# Main_Board_-_Double.net
KiCad netlist of a schematic drawn in EAGLE
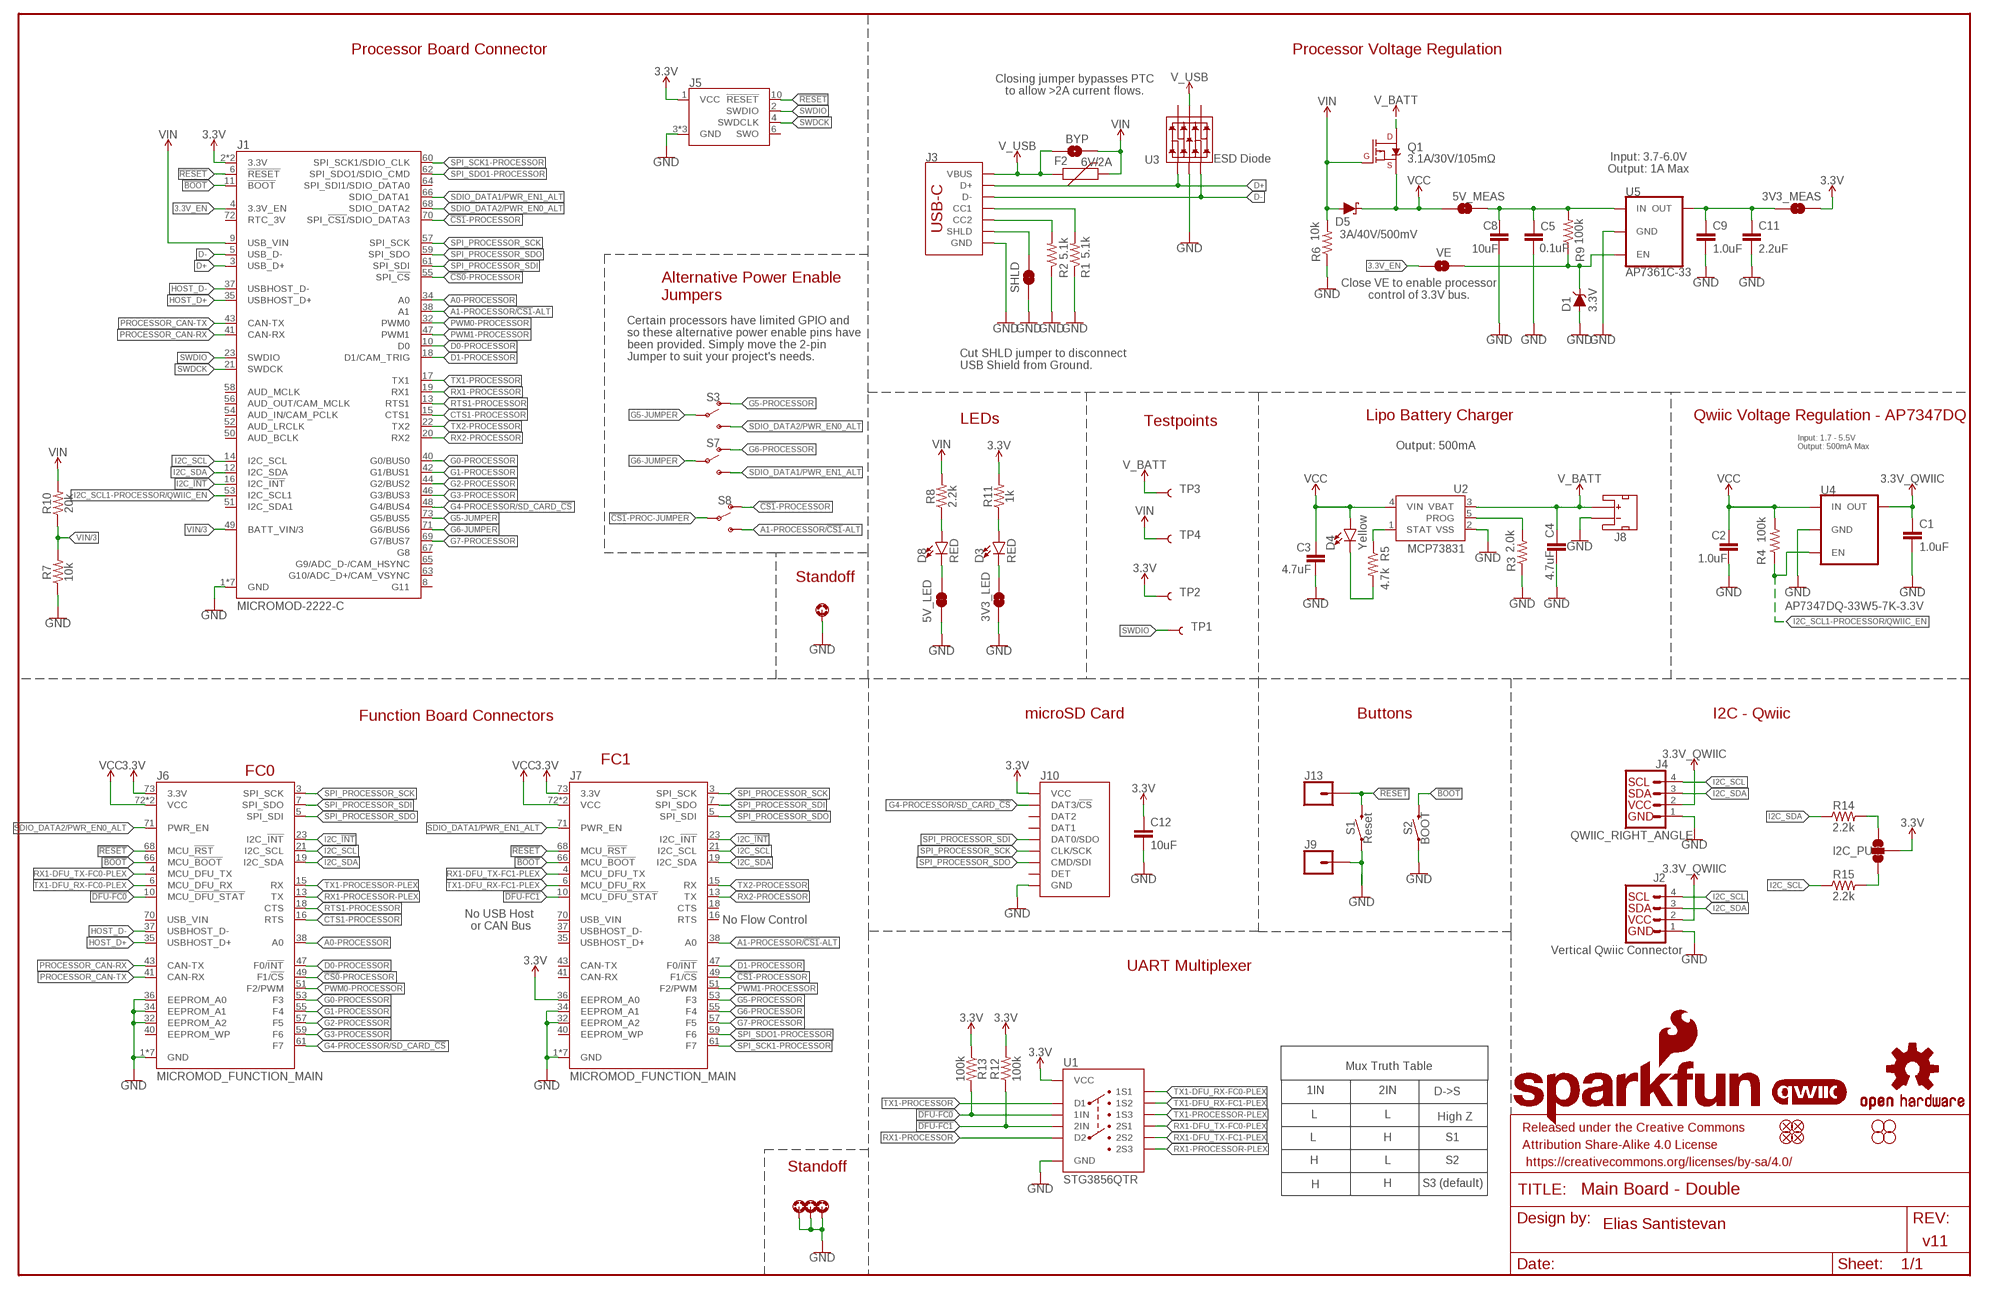
[diagram p0: schematic, sheet 1]

(export (version "E")
  (design (tool "Eeschema 10.0.6"))
  (components
    (comp (ref "3V3_LED")
      (value "JUMPER-SMT_2_NC_TRACE_SILK")
      (footprint "eagle-import:SMT-JUMPER_2_NC_TRACE_SILK")
      (libsource (lib "eagle-import") (part "JUMPER-SMT_2_NC_TRACE_SILK"))
    )
    (comp (ref "3V3_MEAS")
      (value "JUMPER-COMBO_2_NC_TRACE")
      (footprint "eagle-import:COMBO-JUMPER_2_NC_TRACE")
      (libsource (lib "eagle-import") (part "JUMPER-COMBO_2_NC_TRACE"))
    )
    (comp (ref "5V_LED")
      (value "JUMPER-SMT_2_NC_TRACE_SILK")
      (footprint "eagle-import:SMT-JUMPER_2_NC_TRACE_SILK")
      (libsource (lib "eagle-import") (part "JUMPER-SMT_2_NC_TRACE_SILK"))
    )
    (comp (ref "5V_MEAS")
      (value "JUMPER-COMBO_2_NC_TRACE")
      (footprint "eagle-import:COMBO-JUMPER_2_NC_TRACE")
      (libsource (lib "eagle-import") (part "JUMPER-COMBO_2_NC_TRACE"))
    )
    (comp (ref "BYP")
      (value "JUMPER-SMT_2_NO_SILK")
      (footprint "eagle-import:SMT-JUMPER_2_NO_SILK")
      (libsource (lib "eagle-import") (part "JUMPER-SMT_2_NO_SILK"))
    )
    (comp (ref "C1")
      (value "1.0uF")
      (footprint "eagle-import:0603")
      (libsource (lib "eagle-import") (part "1.0UF-0603-16V-10%"))
    )
    (comp (ref "C2")
      (value "1.0uF")
      (footprint "eagle-import:0603")
      (libsource (lib "eagle-import") (part "1.0UF-0603-16V-10%"))
    )
    (comp (ref "C3")
      (value "4.7uF")
      (footprint "eagle-import:0603")
      (libsource (lib "eagle-import") (part "4.7UF-0603-6.3V-(10%)"))
    )
    (comp (ref "C4")
      (value "4.7uF")
      (footprint "eagle-import:0603")
      (libsource (lib "eagle-import") (part "4.7UF-0603-35V-(20%)"))
    )
    (comp (ref "C5")
      (value "0.1uF")
      (footprint "eagle-import:0603")
      (libsource (lib "eagle-import") (part "0.1UF-0603-25V-(+80/-20%)"))
    )
    (comp (ref "C8")
      (value "10uF")
      (footprint "eagle-import:0805")
      (libsource (lib "eagle-import") (part "10UF-0805-10V-10%"))
    )
    (comp (ref "C9")
      (value "1.0uF")
      (footprint "eagle-import:0603")
      (libsource (lib "eagle-import") (part "1.0UF-0603-16V-10%"))
    )
    (comp (ref "C11")
      (value "2.2uF")
      (footprint "eagle-import:0603")
      (libsource (lib "eagle-import") (part "2.2UF-0603-10V-20%"))
    )
    (comp (ref "C12")
      (value "10uF")
      (footprint "eagle-import:0603")
      (libsource (lib "eagle-import") (part "10UF-0603-6.3V-20%"))
    )
    (comp (ref "D1")
      (value "3.3V")
      (footprint "eagle-import:SOD-323")
      (libsource (lib "eagle-import") (part "DIODE-ZENER-MM3Z3V3T1G"))
    )
    (comp (ref "D3")
      (value "RED")
      (footprint "eagle-import:LED-0603")
      (libsource (lib "eagle-import") (part "LED-RED0603"))
    )
    (comp (ref "D4")
      (value "Yellow")
      (footprint "eagle-import:LED-0603")
      (libsource (lib "eagle-import") (part "LED-YELLOW0603"))
    )
    (comp (ref "D5")
      (value "3A/40V/500mV")
      (footprint "eagle-import:SMA-DIODE")
      (libsource (lib "eagle-import") (part "DIODE-SCHOTTKY-B340A"))
    )
    (comp (ref "D8")
      (value "RED")
      (footprint "eagle-import:LED-0603")
      (libsource (lib "eagle-import") (part "LED-RED0603"))
    )
    (comp (ref "F2")
      (value "6V/2A")
      (footprint "eagle-import:1210")
      (libsource (lib "eagle-import") (part "PPTC_6V2A"))
    )
    (comp (ref "FD1")
      (value "FIDUCIAL1X2")
      (footprint "eagle-import:FIDUCIAL-1X2")
      (libsource (lib "eagle-import") (part "FIDUCIAL1X2"))
    )
    (comp (ref "FD2")
      (value "FIDUCIAL1X2")
      (footprint "eagle-import:FIDUCIAL-1X2")
      (libsource (lib "eagle-import") (part "FIDUCIAL1X2"))
    )
    (comp (ref "FD3")
      (value "FIDUCIAL1X2")
      (footprint "eagle-import:FIDUCIAL-1X2")
      (libsource (lib "eagle-import") (part "FIDUCIAL1X2"))
    )
    (comp (ref "FD4")
      (value "FIDUCIAL1X2")
      (footprint "eagle-import:FIDUCIAL-1X2")
      (libsource (lib "eagle-import") (part "FIDUCIAL1X2"))
    )
    (comp (ref "FRAME1")
      (value "FRAME-LEDGER")
      (footprint "eagle-import:CREATIVE_COMMONS")
      (libsource (lib "eagle-import") (part "FRAME-LEDGER"))
    )
    (comp (ref "H2")
      (value "STAND-OFF-REFLOW-M2.5_2.5MM_TALL")
      (footprint "eagle-import:STAND-OFF-REFLOW-M2.5")
      (libsource (lib "eagle-import") (part "STAND-OFF-REFLOW-M2.5_2.5MM_TALL"))
    )
    (comp (ref "H3")
      (value "STAND-OFF-REFLOW-M2.5_2.5MM_TALL")
      (footprint "eagle-import:STAND-OFF-REFLOW-M2.5")
      (libsource (lib "eagle-import") (part "STAND-OFF-REFLOW-M2.5_2.5MM_TALL"))
    )
    (comp (ref "H4")
      (value "STAND-OFF-REFLOW-M2.5_2.5MM_TALL")
      (footprint "eagle-import:STAND-OFF-REFLOW-M2.5")
      (libsource (lib "eagle-import") (part "STAND-OFF-REFLOW-M2.5_2.5MM_TALL"))
    )
    (comp (ref "H8")
      (value "STAND-OFF-REFLOW-M2.5_2.5MM_TALL")
      (footprint "eagle-import:STAND-OFF-REFLOW-M2.5")
      (libsource (lib "eagle-import") (part "STAND-OFF-REFLOW-M2.5_2.5MM_TALL"))
    )
    (comp (ref "H14")
      (value "STAND-OFFTIGHT")
      (footprint "eagle-import:STAND-OFF-TIGHT")
      (libsource (lib "eagle-import") (part "STAND-OFFTIGHT"))
    )
    (comp (ref "H15")
      (value "STAND-OFFTIGHT")
      (footprint "eagle-import:STAND-OFF-TIGHT")
      (libsource (lib "eagle-import") (part "STAND-OFFTIGHT"))
    )
    (comp (ref "H16")
      (value "STAND-OFFTIGHT")
      (footprint "eagle-import:STAND-OFF-TIGHT")
      (libsource (lib "eagle-import") (part "STAND-OFFTIGHT"))
    )
    (comp (ref "H17")
      (value "STAND-OFFTIGHT")
      (footprint "eagle-import:STAND-OFF-TIGHT")
      (libsource (lib "eagle-import") (part "STAND-OFFTIGHT"))
    )
    (comp (ref "I2C_PU")
      (value "JUMPER-SMT_3_2-NC_TRACE_SILK")
      (footprint "eagle-import:SMT-JUMPER_3_2-NC_TRACE_SILK")
      (libsource (lib "eagle-import") (part "JUMPER-SMT_3_2-NC_TRACE_SILK"))
    )
    (comp (ref "J1")
      (value "MICROMOD-2222-C")
      (footprint "eagle-import:M.2-CONNECTOR-E")
      (libsource (lib "eagle-import") (part "MICROMOD-2222-C"))
    )
    (comp (ref "J2")
      (value "Vertical Qwiic Connector")
      (footprint "eagle-import:JST04_1MM_VERT")
      (libsource (lib "eagle-import") (part "QWIIC_CONNECTOR"))
    )
    (comp (ref "J3")
      (value "USB_C_2-LAYER_PADS")
      (footprint "eagle-import:USB-C-16P-2LAYER-PADS")
      (libsource (lib "eagle-import") (part "USB_C_2-LAYER_PADS"))
    )
    (comp (ref "J4")
      (value "QWIIC_RIGHT_ANGLE")
      (footprint "eagle-import:JST04_1MM_RA")
      (libsource (lib "eagle-import") (part "QWIIC_CONNECTORJS-1MM"))
    )
    (comp (ref "J5")
      (value "CORTEX_JTAG_DEBUG_MINIMUM_PTH")
      (footprint "eagle-import:2X5-PTH-1.27MM")
      (libsource (lib "eagle-import") (part "CORTEX_JTAG_DEBUG_MINIMUM_PTH"))
    )
    (comp (ref "J6")
      (value "MICROMOD_FUNCTION_MAIN")
      (footprint "eagle-import:M.2-CONNECTOR-E-FUNCTION-STANDARD")
      (libsource (lib "eagle-import") (part "MICROMOD_FUNCTION_MAIN"))
    )
    (comp (ref "J7")
      (value "MICROMOD_FUNCTION_MAIN")
      (footprint "eagle-import:M.2-CONNECTOR-E-FUNCTION-STANDARD")
      (libsource (lib "eagle-import") (part "MICROMOD_FUNCTION_MAIN"))
    )
    (comp (ref "J8")
      (value "JST_2MM_MALE")
      (footprint "eagle-import:JST-2-SMD")
      (libsource (lib "eagle-import") (part "JST_2MM_MALE"))
    )
    (comp (ref "J9")
      (value "CONN_01PTH_NO_SILK_YES_STOP")
      (footprint "eagle-import:1X01_NO_SILK")
      (libsource (lib "eagle-import") (part "CONN_01PTH_NO_SILK_YES_STOP"))
    )
    (comp (ref "J10")
      (value "MICRO-SD-PUSH-PUSH-EXT-PIN")
      (footprint "eagle-import:MICROSD-EXTERNALPIN")
      (libsource (lib "eagle-import") (part "MICRO-SD-PUSH-PUSH-EXT-PIN"))
    )
    (comp (ref "J13")
      (value "CONN_01PTH_NO_SILK_YES_STOP")
      (footprint "eagle-import:1X01_NO_SILK")
      (libsource (lib "eagle-import") (part "CONN_01PTH_NO_SILK_YES_STOP"))
    )
    (comp (ref "LOGO1")
      (value "QWIIC_LOGO_8MM")
      (footprint "eagle-import:QWIIC_8MM")
      (libsource (lib "eagle-import") (part "QWIIC_LOGO_8MM"))
    )
    (comp (ref "LOGO2")
      (value "SFE_LOGO_NAME_FLAME.3_INCH")
      (footprint "eagle-import:SFE_LOGO_NAME_FLAME_.3")
      (libsource (lib "eagle-import") (part "SFE_LOGO_NAME_FLAME.3_INCH"))
    )
    (comp (ref "LOGO3")
      (value "OSHW-LOGOL")
      (footprint "eagle-import:OSHW-LOGO-L")
      (libsource (lib "eagle-import") (part "OSHW-LOGOL"))
    )
    (comp (ref "Q1")
      (value "3.1A/30V/105mΩ")
      (footprint "eagle-import:SOT23-3")
      (libsource (lib "eagle-import") (part "MOSFET_PCH-DMG2307L"))
    )
    (comp (ref "R1")
      (value "5.1k")
      (footprint "eagle-import:0603")
      (libsource (lib "eagle-import") (part "5.1KOHM5.1KOHM-0603-1/10W-1%"))
    )
    (comp (ref "R2")
      (value "5.1k")
      (footprint "eagle-import:0603")
      (libsource (lib "eagle-import") (part "5.1KOHM5.1KOHM-0603-1/10W-1%"))
    )
    (comp (ref "R3")
      (value "2.0k")
      (footprint "eagle-import:0603")
      (libsource (lib "eagle-import") (part "2.0KOHM-0603-1/10W-5%"))
    )
    (comp (ref "R4")
      (value "100k")
      (footprint "eagle-import:0603")
      (libsource (lib "eagle-import") (part "100KOHM-0603-1/10W-1%"))
    )
    (comp (ref "R5")
      (value "4.7k")
      (footprint "eagle-import:0603")
      (libsource (lib "eagle-import") (part "4.7KOHM-0603-1/10W-1%"))
    )
    (comp (ref "R6")
      (value "10k")
      (footprint "eagle-import:0603")
      (libsource (lib "eagle-import") (part "10KOHM-0603-1/10W-1%"))
    )
    (comp (ref "R7")
      (value "10k")
      (footprint "eagle-import:0603")
      (libsource (lib "eagle-import") (part "10KOHM-0603-1/10W-1%"))
    )
    (comp (ref "R8")
      (value "2.2k")
      (footprint "eagle-import:0603")
      (libsource (lib "eagle-import") (part "2.2KOHM-0603-1/10W-1%"))
    )
    (comp (ref "R9")
      (value "100k")
      (footprint "eagle-import:0603")
      (libsource (lib "eagle-import") (part "100KOHM-0603-1/10W-1%"))
    )
    (comp (ref "R10")
      (value "20k")
      (footprint "eagle-import:0603")
      (libsource (lib "eagle-import") (part "20KOHM-0603-1/10W-1%"))
    )
    (comp (ref "R11")
      (value "1k")
      (footprint "eagle-import:0603")
      (libsource (lib "eagle-import") (part "1KOHM-0603-1/10W-1%"))
    )
    (comp (ref "R12")
      (value "100k")
      (footprint "eagle-import:0603")
      (libsource (lib "eagle-import") (part "100KOHM-0603-1/10W-1%"))
    )
    (comp (ref "R13")
      (value "100k")
      (footprint "eagle-import:0603")
      (libsource (lib "eagle-import") (part "100KOHM-0603-1/10W-1%"))
    )
    (comp (ref "R14")
      (value "2.2k")
      (footprint "eagle-import:0603")
      (libsource (lib "eagle-import") (part "2.2KOHM-0603-1/10W-1%"))
    )
    (comp (ref "R15")
      (value "2.2k")
      (footprint "eagle-import:0603")
      (libsource (lib "eagle-import") (part "2.2KOHM-0603-1/10W-1%"))
    )
    (comp (ref "S1")
      (value "Reset")
      (footprint "eagle-import:TACTILE_SWITCH_SMD_5.2MM")
      (libsource (lib "eagle-import") (part "MOMENTARY-SWITCH-SPST-SMD-5.2-TALL-REDUNDANT"))
    )
    (comp (ref "S2")
      (value "BOOT")
      (footprint "eagle-import:TACTILE_SWITCH_SMD_5.2MM")
      (libsource (lib "eagle-import") (part "MOMENTARY-SWITCH-SPST-SMD-5.2-TALL-REDUNDANT"))
    )
    (comp (ref "S3")
      (value "SWITCH-SPDT-SMD-RIGHT-ANGLE")
      (footprint "eagle-import:SWITCH_SPST_SMD_A")
      (libsource (lib "eagle-import") (part "SWITCH-SPDT-SMD-RIGHT-ANGLE"))
    )
    (comp (ref "S7")
      (value "SWITCH-SPDT-SMD-RIGHT-ANGLE")
      (footprint "eagle-import:SWITCH_SPST_SMD_A")
      (libsource (lib "eagle-import") (part "SWITCH-SPDT-SMD-RIGHT-ANGLE"))
    )
    (comp (ref "S8")
      (value "SWITCH-SPDT-SMD-RIGHT-ANGLE")
      (footprint "eagle-import:SWITCH_SPST_SMD_A")
      (libsource (lib "eagle-import") (part "SWITCH-SPDT-SMD-RIGHT-ANGLE"))
    )
    (comp (ref "SHLD")
      (value "JUMPER-SMT_2_NC_TRACE_SILK")
      (footprint "eagle-import:SMT-JUMPER_2_NC_TRACE_SILK")
      (libsource (lib "eagle-import") (part "JUMPER-SMT_2_NC_TRACE_SILK"))
    )
    (comp (ref "TP1")
      (value "TEST-POINT3X5")
      (footprint "eagle-import:PAD.03X.05")
      (libsource (lib "eagle-import") (part "TEST-POINT3X5"))
    )
    (comp (ref "TP2")
      (value "TEST-POINT3X5")
      (footprint "eagle-import:PAD.03X.05")
      (libsource (lib "eagle-import") (part "TEST-POINT3X5"))
    )
    (comp (ref "TP3")
      (value "TEST-POINT3X5")
      (footprint "eagle-import:PAD.03X.05")
      (libsource (lib "eagle-import") (part "TEST-POINT3X5"))
    )
    (comp (ref "TP4")
      (value "TEST-POINT3X5")
      (footprint "eagle-import:PAD.03X.05")
      (libsource (lib "eagle-import") (part "TEST-POINT3X5"))
    )
    (comp (ref "U1")
      (value "STG3856QTR")
      (footprint "eagle-import:STG3856")
      (libsource (lib "eagle-import") (part "STG3856QTR"))
    )
    (comp (ref "U2")
      (value "MCP73831")
      (footprint "eagle-import:SOT23-5")
      (libsource (lib "eagle-import") (part "MCP73831"))
    )
    (comp (ref "U3")
      (value "ESD Diode")
      (footprint "eagle-import:SOT-23-6")
      (libsource (lib "eagle-import") (part "TVS_DIODE_ARRAYSMD"))
    )
    (comp (ref "U4")
      (value "AP7347DQ-33W5-7K-3.3V")
      (footprint "eagle-import:SOT25")
      (libsource (lib "eagle-import") (part "AP7347DQ-33W5-7K-3.3V"))
    )
    (comp (ref "U5")
      (value "AP7361C-33")
      (footprint "eagle-import:UDFN-8")
      (libsource (lib "eagle-import") (part "AP7361C-33FGEUDFN-8"))
    )
    (comp (ref "VE")
      (value "JUMPER-SMT_2_NO_SILK")
      (footprint "eagle-import:SMT-JUMPER_2_NO_SILK")
      (libsource (lib "eagle-import") (part "JUMPER-SMT_2_NO_SILK"))
    )
  )
  (nets
    (net (code "1") (name "/A1-PROCESSOR{slash}~{CS1}-ALT") (class "Default")
      (node (ref "J1") (pin "38") (pinfunction "A1_38") (pintype "bidirectional"))
      (node (ref "J7") (pin "38") (pinfunction "A0_38") (pintype "bidirectional"))
      (node (ref "S8") (pin "3") (pinfunction "S_3") (pintype "passive"))
    )
    (net (code "2") (name "/G4-PROCESSOR{slash}SD_CARD_~{CS}") (class "Default")
      (node (ref "J1") (pin "48") (pinfunction "G4/BUS4_48") (pintype "bidirectional"))
      (node (ref "J10") (pin "2") (pinfunction "DAT3/~{CS}_2") (pintype "bidirectional"))
      (node (ref "J6") (pin "61") (pinfunction "F7_61") (pintype "bidirectional"))
    )
    (net (code "3") (name "/I2C_~{INT}") (class "Default")
      (node (ref "J1") (pin "16") (pinfunction "I2C_~{INT}_16") (pintype "bidirectional"))
      (node (ref "J6") (pin "23") (pinfunction "I2C_~{INT}_23") (pintype "bidirectional"))
      (node (ref "J7") (pin "23") (pinfunction "I2C_~{INT}_23") (pintype "bidirectional"))
    )
    (net (code "4") (name "/~{BOOT}") (class "Default")
      (node (ref "J1") (pin "11") (pinfunction "~{BOOT}_11") (pintype "bidirectional"))
      (node (ref "J6") (pin "66") (pinfunction "MCU_~{BOOT}_66") (pintype "bidirectional"))
      (node (ref "J7") (pin "66") (pinfunction "MCU_~{BOOT}_66") (pintype "bidirectional"))
      (node (ref "S2") (pin "3") (pinfunction "2_3") (pintype "passive"))
      (node (ref "S2") (pin "4") (pinfunction "2_4") (pintype "passive"))
    )
    (net (code "5") (name "/~{CS0}-PROCESSOR") (class "Default")
      (node (ref "J1") (pin "55") (pinfunction "SPI_~{CS}_55") (pintype "bidirectional"))
      (node (ref "J6") (pin "49") (pinfunction "F1/~{CS}_49") (pintype "bidirectional"))
    )
    (net (code "6") (name "/~{CS1}-PROC-JUMPER") (class "Default")
      (node (ref "S8") (pin "2") (pinfunction "P_2") (pintype "passive"))
    )
    (net (code "7") (name "/~{CS1}-PROCESSOR") (class "Default")
      (node (ref "J1") (pin "70") (pinfunction "SPI_~{CS1}/SDIO_DATA3_70") (pintype "bidirectional"))
      (node (ref "J7") (pin "49") (pinfunction "F1/~{CS}_49") (pintype "bidirectional"))
      (node (ref "S8") (pin "1") (pinfunction "O_1") (pintype "passive"))
    )
    (net (code "8") (name "/~{DFU-FC0}") (class "Default")
      (node (ref "J6") (pin "10") (pinfunction "MCU_~{DFU_STAT}_10") (pintype "bidirectional"))
      (node (ref "R13") (pin "2") (pinfunction "2_2") (pintype "passive"))
      (node (ref "U1") (pin "P12") (pinfunction "1IN_P12") (pintype "bidirectional"))
    )
    (net (code "9") (name "/~{DFU-FC1}") (class "Default")
      (node (ref "J7") (pin "10") (pinfunction "MCU_~{DFU_STAT}_10") (pintype "bidirectional"))
      (node (ref "R12") (pin "1") (pinfunction "1_1") (pintype "passive"))
      (node (ref "U1") (pin "P10") (pinfunction "2IN_P10") (pintype "bidirectional"))
    )
    (net (code "10") (name "/~{RESET}") (class "Default")
      (node (ref "J1") (pin "6") (pinfunction "~{RESET}_6") (pintype "bidirectional"))
      (node (ref "J13") (pin "1") (pinfunction "1_1") (pintype "passive"))
      (node (ref "J5") (pin "10") (pinfunction "~{RESET}_10") (pintype "bidirectional"))
      (node (ref "J6") (pin "68") (pinfunction "MCU_~{RST}_68") (pintype "bidirectional"))
      (node (ref "J7") (pin "68") (pinfunction "MCU_~{RST}_68") (pintype "bidirectional"))
      (node (ref "S1") (pin "3") (pinfunction "2_3") (pintype "passive"))
      (node (ref "S1") (pin "4") (pinfunction "2_4") (pintype "passive"))
    )
    (net (code "11") (name "3.3V") (class "Default")
      (node (ref "3V3_MEAS") (pin "2") (pinfunction "2_2") (pintype "passive"))
      (node (ref "3V3_MEAS") (pin "4") (pinfunction "2_4") (pintype "passive"))
      (node (ref "C12") (pin "1") (pinfunction "1_1") (pintype "passive"))
      (node (ref "I2C_PU") (pin "2") (pinfunction "2_2") (pintype "passive"))
      (node (ref "J1") (pin "2") (pinfunction "3.3V_2") (pintype "bidirectional"))
      (node (ref "J1") (pin "74") (pinfunction "3.3V_74") (pintype "bidirectional"))
      (node (ref "J10") (pin "4") (pinfunction "VCC_4") (pintype "bidirectional"))
      (node (ref "J5") (pin "1") (pinfunction "VCC_1") (pintype "bidirectional"))
      (node (ref "J6") (pin "73") (pinfunction "3.3V_73") (pintype "bidirectional"))
      (node (ref "J7") (pin "36") (pinfunction "EEPROM_A0_36") (pintype "bidirectional"))
      (node (ref "J7") (pin "73") (pinfunction "3.3V_73") (pintype "bidirectional"))
      (node (ref "R11") (pin "2") (pinfunction "2_2") (pintype "passive"))
      (node (ref "R12") (pin "2") (pinfunction "2_2") (pintype "passive"))
      (node (ref "R13") (pin "1") (pinfunction "1_1") (pintype "passive"))
      (node (ref "TP2") (pin "1") (pinfunction "1_1") (pintype "bidirectional"))
      (node (ref "U1") (pin "P11") (pinfunction "VCC_P11") (pintype "power_in"))
    )
    (net (code "12") (name "3.3V_EN") (class "Default")
      (node (ref "J1") (pin "4") (pinfunction "3.3V_EN_4") (pintype "bidirectional"))
      (node (ref "VE") (pin "1") (pinfunction "1_1") (pintype "passive"))
    )
    (net (code "13") (name "3.3V_QWIIC") (class "Default")
      (node (ref "C1") (pin "1") (pinfunction "1_1") (pintype "passive"))
      (node (ref "J2") (pin "2") (pinfunction "2_2") (pintype "power_in"))
      (node (ref "J4") (pin "2") (pinfunction "2_2") (pintype "power_in"))
      (node (ref "U4") (pin "5") (pinfunction "OUT_5") (pintype "passive"))
    )
    (net (code "14") (name "A0-PROCESSOR") (class "Default")
      (node (ref "J1") (pin "34") (pinfunction "A0_34") (pintype "bidirectional"))
      (node (ref "J6") (pin "38") (pinfunction "A0_38") (pintype "bidirectional"))
    )
    (net (code "15") (name "CTS1-PROCESSOR") (class "Default")
      (node (ref "J1") (pin "15") (pinfunction "CTS1_15") (pintype "bidirectional"))
      (node (ref "J6") (pin "16") (pinfunction "RTS_16") (pintype "bidirectional"))
    )
    (net (code "16") (name "D+") (class "Default")
      (node (ref "J1") (pin "3") (pinfunction "USB_D+_3") (pintype "bidirectional"))
      (node (ref "J3") (pin "A6") (pinfunction "D+_A6") (pintype "bidirectional"))
      (node (ref "J3") (pin "B6") (pinfunction "D+_B6") (pintype "bidirectional"))
      (node (ref "U3") (pin "1") (pinfunction "IO1_1") (pintype "bidirectional"))
    )
    (net (code "17") (name "D-") (class "Default")
      (node (ref "J1") (pin "5") (pinfunction "USB_D-_5") (pintype "bidirectional"))
      (node (ref "J3") (pin "A7") (pinfunction "D-_A7") (pintype "bidirectional"))
      (node (ref "J3") (pin "B7") (pinfunction "D-_B7") (pintype "bidirectional"))
      (node (ref "U3") (pin "3") (pinfunction "IO2_3") (pintype "bidirectional"))
    )
    (net (code "18") (name "D0-PROCESSOR") (class "Default")
      (node (ref "J1") (pin "10") (pinfunction "D0_10") (pintype "bidirectional"))
      (node (ref "J6") (pin "47") (pinfunction "F0/~{INT}_47") (pintype "bidirectional"))
    )
    (net (code "19") (name "D1-PROCESSOR") (class "Default")
      (node (ref "J1") (pin "18") (pinfunction "D1/CAM_TRIG_18") (pintype "bidirectional"))
      (node (ref "J7") (pin "47") (pinfunction "F0/~{INT}_47") (pintype "bidirectional"))
    )
    (net (code "20") (name "G0-PROCESSOR") (class "Default")
      (node (ref "J1") (pin "40") (pinfunction "G0/BUS0_40") (pintype "bidirectional"))
      (node (ref "J6") (pin "53") (pinfunction "F3_53") (pintype "bidirectional"))
    )
    (net (code "21") (name "G1-PROCESSOR") (class "Default")
      (node (ref "J1") (pin "42") (pinfunction "G1/BUS1_42") (pintype "bidirectional"))
      (node (ref "J6") (pin "55") (pinfunction "F4_55") (pintype "bidirectional"))
    )
    (net (code "22") (name "G2-PROCESSOR") (class "Default")
      (node (ref "J1") (pin "44") (pinfunction "G2/BUS2_44") (pintype "bidirectional"))
      (node (ref "J6") (pin "57") (pinfunction "F5_57") (pintype "bidirectional"))
    )
    (net (code "23") (name "G3-PROCESSOR") (class "Default")
      (node (ref "J1") (pin "46") (pinfunction "G3/BUS3_46") (pintype "bidirectional"))
      (node (ref "J6") (pin "59") (pinfunction "F6_59") (pintype "bidirectional"))
    )
    (net (code "24") (name "G5-JUMPER") (class "Default")
      (node (ref "J1") (pin "73") (pinfunction "G5/BUS5_73") (pintype "bidirectional"))
      (node (ref "S3") (pin "2") (pinfunction "P_2") (pintype "passive"))
    )
    (net (code "25") (name "G5-PROCESSOR") (class "Default")
      (node (ref "J7") (pin "53") (pinfunction "F3_53") (pintype "bidirectional"))
      (node (ref "S3") (pin "1") (pinfunction "O_1") (pintype "passive"))
    )
    (net (code "26") (name "G6-JUMPER") (class "Default")
      (node (ref "J1") (pin "71") (pinfunction "G6/BUS6_71") (pintype "bidirectional"))
      (node (ref "S7") (pin "2") (pinfunction "P_2") (pintype "passive"))
    )
    (net (code "27") (name "G6-PROCESSOR") (class "Default")
      (node (ref "J7") (pin "55") (pinfunction "F4_55") (pintype "bidirectional"))
      (node (ref "S7") (pin "1") (pinfunction "O_1") (pintype "passive"))
    )
    (net (code "28") (name "G7-PROCESSOR") (class "Default")
      (node (ref "J1") (pin "69") (pinfunction "G7/BUS7_69") (pintype "bidirectional"))
      (node (ref "J7") (pin "57") (pinfunction "F5_57") (pintype "bidirectional"))
    )
    (net (code "29") (name "GND") (class "Default")
      (node (ref "3V3_LED") (pin "1") (pinfunction "1_1") (pintype "passive"))
      (node (ref "5V_LED") (pin "1") (pinfunction "1_1") (pintype "passive"))
      (node (ref "C1") (pin "2") (pinfunction "2_2") (pintype "passive"))
      (node (ref "C11") (pin "2") (pinfunction "2_2") (pintype "passive"))
      (node (ref "C12") (pin "2") (pinfunction "2_2") (pintype "passive"))
      (node (ref "C2") (pin "2") (pinfunction "2_2") (pintype "passive"))
      (node (ref "C3") (pin "2") (pinfunction "2_2") (pintype "passive"))
      (node (ref "C4") (pin "2") (pinfunction "2_2") (pintype "passive"))
      (node (ref "C5") (pin "2") (pinfunction "2_2") (pintype "passive"))
      (node (ref "C8") (pin "2") (pinfunction "2_2") (pintype "passive"))
      (node (ref "C9") (pin "2") (pinfunction "2_2") (pintype "passive"))
      (node (ref "D1") (pin "A") (pinfunction "A_A") (pintype "passive"))
      (node (ref "H2") (pin "1") (pinfunction "1_1") (pintype "bidirectional"))
      (node (ref "H3") (pin "1") (pinfunction "1_1") (pintype "bidirectional"))
      (node (ref "H4") (pin "1") (pinfunction "1_1") (pintype "bidirectional"))
      (node (ref "H8") (pin "1") (pinfunction "1_1") (pintype "bidirectional"))
      (node (ref "J1") (pin "1") (pinfunction "GND_1") (pintype "bidirectional"))
      (node (ref "J1") (pin "33") (pinfunction "GND_33") (pintype "bidirectional"))
      (node (ref "J1") (pin "36") (pinfunction "GND_36") (pintype "bidirectional"))
      (node (ref "J1") (pin "39") (pinfunction "GND_39") (pintype "bidirectional"))
      (node (ref "J1") (pin "45") (pinfunction "GND_45") (pintype "bidirectional"))
      (node (ref "J1") (pin "7") (pinfunction "GND_7") (pintype "bidirectional"))
      (node (ref "J1") (pin "75") (pinfunction "GND_75") (pintype "bidirectional"))
      (node (ref "J10") (pin "10") (pinfunction "GND_10") (pintype "bidirectional"))
      (node (ref "J10") (pin "11") (pinfunction "GND_11") (pintype "bidirectional"))
      (node (ref "J10") (pin "12") (pinfunction "GND_12") (pintype "bidirectional"))
      (node (ref "J10") (pin "13") (pinfunction "GND_13") (pintype "bidirectional"))
      (node (ref "J10") (pin "6") (pinfunction "GND_6") (pintype "bidirectional"))
      (node (ref "J2") (pin "1") (pinfunction "1_1") (pintype "power_in"))
      (node (ref "J3") (pin "GND") (pinfunction "GND_GND") (pintype "bidirectional"))
      (node (ref "J3") (pin "GND2") (pinfunction "GND_GND2") (pintype "bidirectional"))
      (node (ref "J4") (pin "1") (pinfunction "1_1") (pintype "power_in"))
      (node (ref "J5") (pin "3") (pinfunction "GND_3") (pintype "bidirectional"))
      (node (ref "J5") (pin "5") (pinfunction "GND_5") (pintype "bidirectional"))
      (node (ref "J5") (pin "9") (pinfunction "GND_9") (pintype "bidirectional"))
      (node (ref "J6") (pin "1") (pinfunction "GND_1") (pintype "bidirectional"))
      (node (ref "J6") (pin "2") (pinfunction "GND_2") (pintype "bidirectional"))
      (node (ref "J6") (pin "32") (pinfunction "EEPROM_A2_32") (pintype "bidirectional"))
      (node (ref "J6") (pin "33") (pinfunction "GND_33") (pintype "bidirectional"))
      (node (ref "J6") (pin "34") (pinfunction "EEPROM_A1_34") (pintype "bidirectional"))
      (node (ref "J6") (pin "36") (pinfunction "EEPROM_A0_36") (pintype "bidirectional"))
      (node (ref "J6") (pin "39") (pinfunction "GND_39") (pintype "bidirectional"))
      (node (ref "J6") (pin "45") (pinfunction "GND_45") (pintype "bidirectional"))
      (node (ref "J6") (pin "75") (pinfunction "GND_75") (pintype "bidirectional"))
      (node (ref "J6") (pin "8") (pinfunction "GND_8") (pintype "bidirectional"))
      (node (ref "J7") (pin "1") (pinfunction "GND_1") (pintype "bidirectional"))
      (node (ref "J7") (pin "2") (pinfunction "GND_2") (pintype "bidirectional"))
      (node (ref "J7") (pin "32") (pinfunction "EEPROM_A2_32") (pintype "bidirectional"))
      (node (ref "J7") (pin "33") (pinfunction "GND_33") (pintype "bidirectional"))
      (node (ref "J7") (pin "34") (pinfunction "EEPROM_A1_34") (pintype "bidirectional"))
      (node (ref "J7") (pin "39") (pinfunction "GND_39") (pintype "bidirectional"))
      (node (ref "J7") (pin "45") (pinfunction "GND_45") (pintype "bidirectional"))
      (node (ref "J7") (pin "75") (pinfunction "GND_75") (pintype "bidirectional"))
      (node (ref "J7") (pin "8") (pinfunction "GND_8") (pintype "bidirectional"))
      (node (ref "J8") (pin "1") (pinfunction "-_1") (pintype "bidirectional"))
      (node (ref "J9") (pin "1") (pinfunction "1_1") (pintype "passive"))
      (node (ref "R1") (pin "1") (pinfunction "1_1") (pintype "passive"))
      (node (ref "R2") (pin "1") (pinfunction "1_1") (pintype "passive"))
      (node (ref "R3") (pin "1") (pinfunction "1_1") (pintype "passive"))
      (node (ref "R6") (pin "1") (pinfunction "1_1") (pintype "passive"))
      (node (ref "R7") (pin "1") (pinfunction "1_1") (pintype "passive"))
      (node (ref "S1") (pin "1") (pinfunction "1_1") (pintype "passive"))
      (node (ref "S1") (pin "2") (pinfunction "1_2") (pintype "passive"))
      (node (ref "S2") (pin "1") (pinfunction "1_1") (pintype "passive"))
      (node (ref "S2") (pin "2") (pinfunction "1_2") (pintype "passive"))
      (node (ref "SHLD") (pin "1") (pinfunction "1_1") (pintype "passive"))
      (node (ref "U1") (pin "P5") (pinfunction "GND_P5") (pintype "power_in"))
      (node (ref "U2") (pin "2") (pinfunction "VSS_2") (pintype "power_in"))
      (node (ref "U3") (pin "2") (pinfunction "VSS_2") (pintype "bidirectional"))
      (node (ref "U4") (pin "2") (pinfunction "GND_2") (pintype "input"))
      (node (ref "U5") (pin "4") (pinfunction "GND_4") (pintype "input"))
      (node (ref "U5") (pin "EP") (pinfunction "GND_EP") (pintype "input"))
    )
    (net (code "30") (name "HOST_D+") (class "Default")
      (node (ref "J1") (pin "35") (pinfunction "USBHOST_D+_35") (pintype "bidirectional"))
      (node (ref "J6") (pin "35") (pinfunction "USBHOST_D+_35") (pintype "bidirectional"))
    )
    (net (code "31") (name "HOST_D-") (class "Default")
      (node (ref "J1") (pin "37") (pinfunction "USBHOST_D-_37") (pintype "bidirectional"))
      (node (ref "J6") (pin "37") (pinfunction "USBHOST_D-_37") (pintype "bidirectional"))
    )
    (net (code "32") (name "I2C_SCL") (class "Default")
      (node (ref "J1") (pin "14") (pinfunction "I2C_SCL_14") (pintype "bidirectional"))
      (node (ref "J2") (pin "4") (pinfunction "4_4") (pintype "passive"))
      (node (ref "J4") (pin "4") (pinfunction "4_4") (pintype "passive"))
      (node (ref "J6") (pin "21") (pinfunction "I2C_SCL_21") (pintype "bidirectional"))
      (node (ref "J7") (pin "21") (pinfunction "I2C_SCL_21") (pintype "bidirectional"))
      (node (ref "R15") (pin "1") (pinfunction "1_1") (pintype "passive"))
    )
    (net (code "33") (name "I2C_SCL1-PROCESSOR{slash}QWIIC_EN") (class "Default")
      (node (ref "J1") (pin "53") (pinfunction "I2C_SCL1_53") (pintype "bidirectional"))
      (node (ref "R4") (pin "1") (pinfunction "1_1") (pintype "passive"))
      (node (ref "U4") (pin "3") (pinfunction "EN_3") (pintype "input"))
    )
    (net (code "34") (name "I2C_SDA") (class "Default")
      (node (ref "J1") (pin "12") (pinfunction "I2C_SDA_12") (pintype "bidirectional"))
      (node (ref "J2") (pin "3") (pinfunction "3_3") (pintype "passive"))
      (node (ref "J4") (pin "3") (pinfunction "3_3") (pintype "passive"))
      (node (ref "J6") (pin "19") (pinfunction "I2C_SDA_19") (pintype "bidirectional"))
      (node (ref "J7") (pin "19") (pinfunction "I2C_SDA_19") (pintype "bidirectional"))
      (node (ref "R14") (pin "1") (pinfunction "1_1") (pintype "passive"))
    )
    (net (code "35") (name "Net-(3V3_LED-Pad2)") (class "Default")
      (node (ref "3V3_LED") (pin "2") (pinfunction "2_2") (pintype "passive"))
      (node (ref "D3") (pin "C") (pinfunction "C_C") (pintype "passive"))
    )
    (net (code "36") (name "Net-(5V_LED-Pad2)") (class "Default")
      (node (ref "5V_LED") (pin "2") (pinfunction "2_2") (pintype "passive"))
      (node (ref "D8") (pin "C") (pinfunction "C_C") (pintype "passive"))
    )
    (net (code "37") (name "Net-(D3-PadA)") (class "Default")
      (node (ref "D3") (pin "A") (pinfunction "A_A") (pintype "passive"))
      (node (ref "R11") (pin "1") (pinfunction "1_1") (pintype "passive"))
    )
    (net (code "38") (name "Net-(D4-PadC)") (class "Default")
      (node (ref "D4") (pin "C") (pinfunction "C_C") (pintype "passive"))
      (node (ref "R5") (pin "2") (pinfunction "2_2") (pintype "passive"))
    )
    (net (code "39") (name "Net-(D8-PadA)") (class "Default")
      (node (ref "D8") (pin "A") (pinfunction "A_A") (pintype "passive"))
      (node (ref "R8") (pin "1") (pinfunction "1_1") (pintype "passive"))
    )
    (net (code "40") (name "Net-(I2C_PU-Pad1)") (class "Default")
      (node (ref "I2C_PU") (pin "1") (pinfunction "1_1") (pintype "passive"))
      (node (ref "R15") (pin "2") (pinfunction "2_2") (pintype "passive"))
    )
    (net (code "41") (name "Net-(I2C_PU-Pad3)") (class "Default")
      (node (ref "I2C_PU") (pin "3") (pinfunction "3_3") (pintype "passive"))
      (node (ref "R14") (pin "2") (pinfunction "2_2") (pintype "passive"))
    )
    (net (code "42") (name "Net-(J3-CC1)") (class "Default")
      (node (ref "J3") (pin "A5") (pinfunction "CC1_A5") (pintype "bidirectional"))
      (node (ref "R1") (pin "2") (pinfunction "2_2") (pintype "passive"))
    )
    (net (code "43") (name "Net-(J3-CC2)") (class "Default")
      (node (ref "J3") (pin "B5") (pinfunction "CC2_B5") (pintype "bidirectional"))
      (node (ref "R2") (pin "2") (pinfunction "2_2") (pintype "passive"))
    )
    (net (code "44") (name "Net-(J3-SHLD-PadSHLD1)") (class "Default")
      (node (ref "J3") (pin "SHLD1") (pinfunction "SHLD_SHLD1") (pintype "bidirectional"))
      (node (ref "J3") (pin "SHLD2") (pinfunction "SHLD_SHLD2") (pintype "bidirectional"))
      (node (ref "J3") (pin "SHLD3") (pinfunction "SHLD_SHLD3") (pintype "bidirectional"))
      (node (ref "J3") (pin "SHLD4") (pinfunction "SHLD_SHLD4") (pintype "bidirectional"))
      (node (ref "SHLD") (pin "2") (pinfunction "2_2") (pintype "passive"))
    )
    (net (code "45") (name "Net-(U2-PROG)") (class "Default")
      (node (ref "R3") (pin "2") (pinfunction "2_2") (pintype "passive"))
      (node (ref "U2") (pin "5") (pinfunction "PROG_5") (pintype "input"))
    )
    (net (code "46") (name "Net-(U2-STAT)") (class "Default")
      (node (ref "R5") (pin "1") (pinfunction "1_1") (pintype "passive"))
      (node (ref "U2") (pin "1") (pinfunction "STAT_1") (pintype "output"))
    )
    (net (code "47") (name "Net-(U5-EN)") (class "Default")
      (node (ref "D1") (pin "C") (pinfunction "C_C") (pintype "passive"))
      (node (ref "R9") (pin "1") (pinfunction "1_1") (pintype "passive"))
      (node (ref "U5") (pin "5") (pinfunction "EN_5") (pintype "bidirectional"))
      (node (ref "VE") (pin "2") (pinfunction "2_2") (pintype "passive"))
    )
    (net (code "48") (name "Net-(U5-IN)") (class "Default")
      (node (ref "5V_MEAS") (pin "2") (pinfunction "2_2") (pintype "passive"))
      (node (ref "5V_MEAS") (pin "4") (pinfunction "2_4") (pintype "passive"))
      (node (ref "C5") (pin "1") (pinfunction "1_1") (pintype "passive"))
      (node (ref "C8") (pin "1") (pinfunction "1_1") (pintype "passive"))
      (node (ref "R9") (pin "2") (pinfunction "2_2") (pintype "passive"))
      (node (ref "U5") (pin "8") (pinfunction "IN_8") (pintype "input"))
    )
    (net (code "49") (name "Net-(U5-OUT)") (class "Default")
      (node (ref "3V3_MEAS") (pin "1") (pinfunction "1_1") (pintype "passive"))
      (node (ref "3V3_MEAS") (pin "3") (pinfunction "1_3") (pintype "passive"))
      (node (ref "C11") (pin "1") (pinfunction "1_1") (pintype "passive"))
      (node (ref "C9") (pin "1") (pinfunction "1_1") (pintype "passive"))
      (node (ref "U5") (pin "1") (pinfunction "OUT_1") (pintype "output"))
    )
    (net (code "50") (name "PROCESSOR_CAN-RX") (class "Default")
      (node (ref "J1") (pin "41") (pinfunction "CAN-RX_41") (pintype "bidirectional"))
      (node (ref "J6") (pin "43") (pinfunction "CAN-TX_43") (pintype "bidirectional"))
    )
    (net (code "51") (name "PROCESSOR_CAN-TX") (class "Default")
      (node (ref "J1") (pin "43") (pinfunction "CAN-TX_43") (pintype "bidirectional"))
      (node (ref "J6") (pin "41") (pinfunction "CAN-RX_41") (pintype "bidirectional"))
    )
    (net (code "52") (name "PWM0-PROCESSOR") (class "Default")
      (node (ref "J1") (pin "32") (pinfunction "PWM0_32") (pintype "bidirectional"))
      (node (ref "J6") (pin "51") (pinfunction "F2/PWM_51") (pintype "bidirectional"))
    )
    (net (code "53") (name "PWM1-PROCESSOR") (class "Default")
      (node (ref "J1") (pin "47") (pinfunction "PWM1_47") (pintype "bidirectional"))
      (node (ref "J7") (pin "51") (pinfunction "F2/PWM_51") (pintype "bidirectional"))
    )
    (net (code "54") (name "RTS1-PROCESSOR") (class "Default")
      (node (ref "J1") (pin "13") (pinfunction "RTS1_13") (pintype "bidirectional"))
      (node (ref "J6") (pin "18") (pinfunction "CTS_18") (pintype "bidirectional"))
    )
    (net (code "55") (name "RX1-DFU_TX-FC0-PLEX") (class "Default")
      (node (ref "J6") (pin "4") (pinfunction "MCU_DFU_TX_4") (pintype "bidirectional"))
      (node (ref "U1") (pin "P9") (pinfunction "2S1_P9") (pintype "bidirectional"))
    )
    (net (code "56") (name "RX1-DFU_TX-FC1-PLEX") (class "Default")
      (node (ref "J7") (pin "4") (pinfunction "MCU_DFU_TX_4") (pintype "bidirectional"))
      (node (ref "U1") (pin "P8") (pinfunction "2S2_P8") (pintype "bidirectional"))
    )
    (net (code "57") (name "RX1-PROCESSOR") (class "Default")
      (node (ref "J1") (pin "19") (pinfunction "RX1_19") (pintype "bidirectional"))
      (node (ref "U1") (pin "P6") (pinfunction "D2_P6") (pintype "bidirectional"))
    )
    (net (code "58") (name "RX1-PROCESSOR-PLEX") (class "Default")
      (node (ref "J6") (pin "13") (pinfunction "TX_13") (pintype "bidirectional"))
      (node (ref "U1") (pin "P7") (pinfunction "2S3_P7") (pintype "bidirectional"))
    )
    (net (code "59") (name "RX2-PROCESSOR") (class "Default")
      (node (ref "J1") (pin "20") (pinfunction "RX2_20") (pintype "bidirectional"))
      (node (ref "J7") (pin "13") (pinfunction "TX_13") (pintype "bidirectional"))
    )
    (net (code "60") (name "SDIO_DATA1{slash}PWR_EN1_ALT") (class "Default")
      (node (ref "J1") (pin "66") (pinfunction "SDIO_DATA1_66") (pintype "bidirectional"))
      (node (ref "J7") (pin "71") (pinfunction "PWR_EN_71") (pintype "bidirectional"))
      (node (ref "S7") (pin "3") (pinfunction "S_3") (pintype "passive"))
    )
    (net (code "61") (name "SDIO_DATA2{slash}PWR_EN0_ALT") (class "Default")
      (node (ref "J1") (pin "68") (pinfunction "SDIO_DATA2_68") (pintype "bidirectional"))
      (node (ref "J6") (pin "71") (pinfunction "PWR_EN_71") (pintype "bidirectional"))
      (node (ref "S3") (pin "3") (pinfunction "S_3") (pintype "passive"))
    )
    (net (code "62") (name "SPI_PROCESSOR_SCK") (class "Default")
      (node (ref "J1") (pin "57") (pinfunction "SPI_SCK_57") (pintype "bidirectional"))
      (node (ref "J10") (pin "5") (pinfunction "CLK/SCK_5") (pintype "bidirectional"))
      (node (ref "J6") (pin "3") (pinfunction "SPI_SCK_3") (pintype "bidirectional"))
      (node (ref "J7") (pin "3") (pinfunction "SPI_SCK_3") (pintype "bidirectional"))
    )
    (net (code "63") (name "SPI_PROCESSOR_SDI") (class "Default")
      (node (ref "J1") (pin "61") (pinfunction "SPI_SDI_61") (pintype "bidirectional"))
      (node (ref "J10") (pin "7") (pinfunction "DAT0/SDO_7") (pintype "bidirectional"))
      (node (ref "J6") (pin "7") (pinfunction "SPI_SDO_7") (pintype "bidirectional"))
      (node (ref "J7") (pin "7") (pinfunction "SPI_SDO_7") (pintype "bidirectional"))
    )
    (net (code "64") (name "SPI_PROCESSOR_SDO") (class "Default")
      (node (ref "J1") (pin "59") (pinfunction "SPI_SDO_59") (pintype "bidirectional"))
      (node (ref "J10") (pin "3") (pinfunction "CMD/SDI_3") (pintype "bidirectional"))
      (node (ref "J6") (pin "5") (pinfunction "SPI_SDI_5") (pintype "bidirectional"))
      (node (ref "J7") (pin "5") (pinfunction "SPI_SDI_5") (pintype "bidirectional"))
    )
    (net (code "65") (name "SPI_SCK1-PROCESSOR") (class "Default")
      (node (ref "J1") (pin "60") (pinfunction "SPI_SCK1/SDIO_CLK_60") (pintype "bidirectional"))
      (node (ref "J7") (pin "61") (pinfunction "F7_61") (pintype "bidirectional"))
    )
    (net (code "66") (name "SPI_SDO1-PROCESSOR") (class "Default")
      (node (ref "J1") (pin "62") (pinfunction "SPI_SDO1/SDIO_CMD_62") (pintype "bidirectional"))
      (node (ref "J7") (pin "59") (pinfunction "F6_59") (pintype "bidirectional"))
    )
    (net (code "67") (name "SWDCK") (class "Default")
      (node (ref "J1") (pin "21") (pinfunction "SWDCK_21") (pintype "bidirectional"))
      (node (ref "J5") (pin "4") (pinfunction "SWDCLK_4") (pintype "bidirectional"))
    )
    (net (code "68") (name "SWDIO") (class "Default")
      (node (ref "J1") (pin "23") (pinfunction "SWDIO_23") (pintype "bidirectional"))
      (node (ref "J5") (pin "2") (pinfunction "SWDIO_2") (pintype "bidirectional"))
      (node (ref "TP1") (pin "1") (pinfunction "1_1") (pintype "bidirectional"))
    )
    (net (code "69") (name "TX1-DFU_RX-FC0-PLEX") (class "Default")
      (node (ref "J6") (pin "6") (pinfunction "MCU_DFU_RX_6") (pintype "bidirectional"))
      (node (ref "U1") (pin "P1") (pinfunction "1S1_P1") (pintype "bidirectional"))
    )
    (net (code "70") (name "TX1-DFU_RX-FC1-PLEX") (class "Default")
      (node (ref "J7") (pin "6") (pinfunction "MCU_DFU_RX_6") (pintype "bidirectional"))
      (node (ref "U1") (pin "P2") (pinfunction "1S2_P2") (pintype "bidirectional"))
    )
    (net (code "71") (name "TX1-PROCESSOR") (class "Default")
      (node (ref "J1") (pin "17") (pinfunction "TX1_17") (pintype "bidirectional"))
      (node (ref "U1") (pin "P4") (pinfunction "D1_P4") (pintype "bidirectional"))
    )
    (net (code "72") (name "TX1-PROCESSOR-PLEX") (class "Default")
      (node (ref "J6") (pin "15") (pinfunction "RX_15") (pintype "bidirectional"))
      (node (ref "U1") (pin "P3") (pinfunction "1S3_P3") (pintype "bidirectional"))
    )
    (net (code "73") (name "TX2-PROCESSOR") (class "Default")
      (node (ref "J1") (pin "22") (pinfunction "TX2_22") (pintype "bidirectional"))
      (node (ref "J7") (pin "15") (pinfunction "RX_15") (pintype "bidirectional"))
    )
    (net (code "74") (name "VCC") (class "Default")
      (node (ref "5V_MEAS") (pin "1") (pinfunction "1_1") (pintype "passive"))
      (node (ref "5V_MEAS") (pin "3") (pinfunction "1_3") (pintype "passive"))
      (node (ref "C2") (pin "1") (pinfunction "1_1") (pintype "passive"))
      (node (ref "C3") (pin "1") (pinfunction "1_1") (pintype "passive"))
      (node (ref "D4") (pin "A") (pinfunction "A_A") (pintype "passive"))
      (node (ref "D5") (pin "C") (pinfunction "C_C") (pintype "passive"))
      (node (ref "J6") (pin "72") (pinfunction "VCC_72") (pintype "bidirectional"))
      (node (ref "J6") (pin "74") (pinfunction "VCC_74") (pintype "bidirectional"))
      (node (ref "J7") (pin "72") (pinfunction "VCC_72") (pintype "bidirectional"))
      (node (ref "J7") (pin "74") (pinfunction "VCC_74") (pintype "bidirectional"))
      (node (ref "Q1") (pin "2") (pinfunction "S_2") (pintype "bidirectional"))
      (node (ref "R4") (pin "2") (pinfunction "2_2") (pintype "passive"))
      (node (ref "U2") (pin "4") (pinfunction "VIN_4") (pintype "power_in"))
      (node (ref "U4") (pin "1") (pinfunction "IN_1") (pintype "input"))
    )
    (net (code "75") (name "VIN") (class "Default")
      (node (ref "BYP") (pin "2") (pinfunction "2_2") (pintype "passive"))
      (node (ref "D5") (pin "A") (pinfunction "A_A") (pintype "passive"))
      (node (ref "F2") (pin "2") (pinfunction "2_2") (pintype "bidirectional"))
      (node (ref "J1") (pin "9") (pinfunction "USB_VIN_9") (pintype "bidirectional"))
      (node (ref "Q1") (pin "1") (pinfunction "G_1") (pintype "bidirectional"))
      (node (ref "R10") (pin "2") (pinfunction "2_2") (pintype "passive"))
      (node (ref "R6") (pin "2") (pinfunction "2_2") (pintype "passive"))
      (node (ref "R8") (pin "2") (pinfunction "2_2") (pintype "passive"))
      (node (ref "TP4") (pin "1") (pinfunction "1_1") (pintype "bidirectional"))
    )
    (net (code "76") (name "VIN{slash}3") (class "Default")
      (node (ref "J1") (pin "49") (pinfunction "BATT_VIN/3_49") (pintype "bidirectional"))
      (node (ref "R10") (pin "1") (pinfunction "1_1") (pintype "passive"))
      (node (ref "R7") (pin "2") (pinfunction "2_2") (pintype "passive"))
    )
    (net (code "77") (name "V_BATT") (class "Default")
      (node (ref "C4") (pin "1") (pinfunction "1_1") (pintype "passive"))
      (node (ref "J8") (pin "2") (pinfunction "+_2") (pintype "bidirectional"))
      (node (ref "Q1") (pin "3") (pinfunction "D_3") (pintype "bidirectional"))
      (node (ref "TP3") (pin "1") (pinfunction "1_1") (pintype "bidirectional"))
      (node (ref "U2") (pin "3") (pinfunction "VBAT_3") (pintype "power_in"))
    )
    (net (code "78") (name "V_USB") (class "Default")
      (node (ref "BYP") (pin "1") (pinfunction "1_1") (pintype "passive"))
      (node (ref "F2") (pin "1") (pinfunction "1_1") (pintype "bidirectional"))
      (node (ref "J3") (pin "VBUS1") (pinfunction "VBUS_VBUS1") (pintype "bidirectional"))
      (node (ref "J3") (pin "VBUS2") (pinfunction "VBUS_VBUS2") (pintype "bidirectional"))
      (node (ref "U3") (pin "5") (pinfunction "VCC_5") (pintype "bidirectional"))
    )
    (net (code "79") (name "unconnected-(J1-AUD_BCLK-Pad50)") (class "Default")
      (node (ref "J1") (pin "50") (pinfunction "AUD_BCLK_50") (pintype "bidirectional"))
    )
    (net (code "80") (name "unconnected-(J1-AUD_IN{slash}CAM_PCLK-Pad54)") (class "Default")
      (node (ref "J1") (pin "54") (pinfunction "AUD_IN/CAM_PCLK_54") (pintype "bidirectional"))
    )
    (net (code "81") (name "unconnected-(J1-AUD_LRCLK-Pad52)") (class "Default")
      (node (ref "J1") (pin "52") (pinfunction "AUD_LRCLK_52") (pintype "bidirectional"))
    )
    (net (code "82") (name "unconnected-(J1-AUD_MCLK-Pad58)") (class "Default")
      (node (ref "J1") (pin "58") (pinfunction "AUD_MCLK_58") (pintype "bidirectional"))
    )
    (net (code "83") (name "unconnected-(J1-AUD_OUT{slash}CAM_MCLK-Pad56)") (class "Default")
      (node (ref "J1") (pin "56") (pinfunction "AUD_OUT/CAM_MCLK_56") (pintype "bidirectional"))
    )
    (net (code "84") (name "unconnected-(J1-G8-Pad67)") (class "Default")
      (node (ref "J1") (pin "67") (pinfunction "G8_67") (pintype "bidirectional"))
    )
    (net (code "85") (name "unconnected-(J1-G9{slash}ADC_D-{slash}CAM_HSYNC-Pad65)") (class "Default")
      (node (ref "J1") (pin "65") (pinfunction "G9/ADC_D-/CAM_HSYNC_65") (pintype "bidirectional"))
    )
    (net (code "86") (name "unconnected-(J1-G10{slash}ADC_D+{slash}CAM_VSYNC-Pad63)") (class "Default")
      (node (ref "J1") (pin "63") (pinfunction "G10/ADC_D+/CAM_VSYNC_63") (pintype "bidirectional"))
    )
    (net (code "87") (name "unconnected-(J1-G11-Pad8)") (class "Default")
      (node (ref "J1") (pin "8") (pinfunction "G11_8") (pintype "bidirectional"))
    )
    (net (code "88") (name "unconnected-(J1-I2C_SDA1-Pad51)") (class "Default")
      (node (ref "J1") (pin "51") (pinfunction "I2C_SDA1_51") (pintype "bidirectional"))
    )
    (net (code "89") (name "unconnected-(J1-RTC_3V-Pad72)") (class "Default")
      (node (ref "J1") (pin "72") (pinfunction "RTC_3V_72") (pintype "bidirectional"))
    )
    (net (code "90") (name "unconnected-(J1-SPI_SDI1{slash}SDIO_DATA0-Pad64)") (class "Default")
      (node (ref "J1") (pin "64") (pinfunction "SPI_SDI1/SDIO_DATA0_64") (pintype "bidirectional"))
    )
    (net (code "91") (name "unconnected-(J5-SWO-Pad6)") (class "Default")
      (node (ref "J5") (pin "6") (pinfunction "SWO_6") (pintype "bidirectional"))
    )
    (net (code "92") (name "unconnected-(J6-EEPROM_WP-Pad40)") (class "Default")
      (node (ref "J6") (pin "40") (pinfunction "EEPROM_WP_40") (pintype "bidirectional"))
    )
    (net (code "93") (name "unconnected-(J6-USB_VIN-Pad70)") (class "Default")
      (node (ref "J6") (pin "70") (pinfunction "USB_VIN_70") (pintype "bidirectional"))
    )
    (net (code "94") (name "unconnected-(J7-CAN-RX-Pad41)") (class "Default")
      (node (ref "J7") (pin "41") (pinfunction "CAN-RX_41") (pintype "bidirectional"))
    )
    (net (code "95") (name "unconnected-(J7-CAN-TX-Pad43)") (class "Default")
      (node (ref "J7") (pin "43") (pinfunction "CAN-TX_43") (pintype "bidirectional"))
    )
    (net (code "96") (name "unconnected-(J7-CTS-Pad18)") (class "Default")
      (node (ref "J7") (pin "18") (pinfunction "CTS_18") (pintype "bidirectional"))
    )
    (net (code "97") (name "unconnected-(J7-EEPROM_WP-Pad40)") (class "Default")
      (node (ref "J7") (pin "40") (pinfunction "EEPROM_WP_40") (pintype "bidirectional"))
    )
    (net (code "98") (name "unconnected-(J7-RTS-Pad16)") (class "Default")
      (node (ref "J7") (pin "16") (pinfunction "RTS_16") (pintype "bidirectional"))
    )
    (net (code "99") (name "unconnected-(J7-USBHOST_D+-Pad35)") (class "Default")
      (node (ref "J7") (pin "35") (pinfunction "USBHOST_D+_35") (pintype "bidirectional"))
    )
    (net (code "100") (name "unconnected-(J7-USBHOST_D--Pad37)") (class "Default")
      (node (ref "J7") (pin "37") (pinfunction "USBHOST_D-_37") (pintype "bidirectional"))
    )
    (net (code "101") (name "unconnected-(J7-USB_VIN-Pad70)") (class "Default")
      (node (ref "J7") (pin "70") (pinfunction "USB_VIN_70") (pintype "bidirectional"))
    )
    (net (code "102") (name "unconnected-(J8-PAD1-PadNC1)") (class "Default")
      (node (ref "J8") (pin "NC1") (pinfunction "PAD1_NC1") (pintype "bidirectional"))
    )
    (net (code "103") (name "unconnected-(J8-PAD2-PadNC2)") (class "Default")
      (node (ref "J8") (pin "NC2") (pinfunction "PAD2_NC2") (pintype "bidirectional"))
    )
    (net (code "104") (name "unconnected-(J10-DAT1-Pad8)") (class "Default")
      (node (ref "J10") (pin "8") (pinfunction "DAT1_8") (pintype "bidirectional"))
    )
    (net (code "105") (name "unconnected-(J10-DAT2-Pad1)") (class "Default")
      (node (ref "J10") (pin "1") (pinfunction "DAT2_1") (pintype "bidirectional"))
    )
    (net (code "106") (name "unconnected-(J10-DET-Pad9)") (class "Default")
      (node (ref "J10") (pin "9") (pinfunction "DET_9") (pintype "bidirectional"))
    )
    (net (code "107") (name "unconnected-(U3-IO3-Pad4)") (class "Default")
      (node (ref "U3") (pin "4") (pinfunction "IO3_4") (pintype "bidirectional"))
    )
    (net (code "108") (name "unconnected-(U3-IO4-Pad6)") (class "Default")
      (node (ref "U3") (pin "6") (pinfunction "IO4_6") (pintype "bidirectional"))
    )
  )
)
